# Laser_Tec_Control.net
KiCad netlist of a schematic drawn in Altium Designer
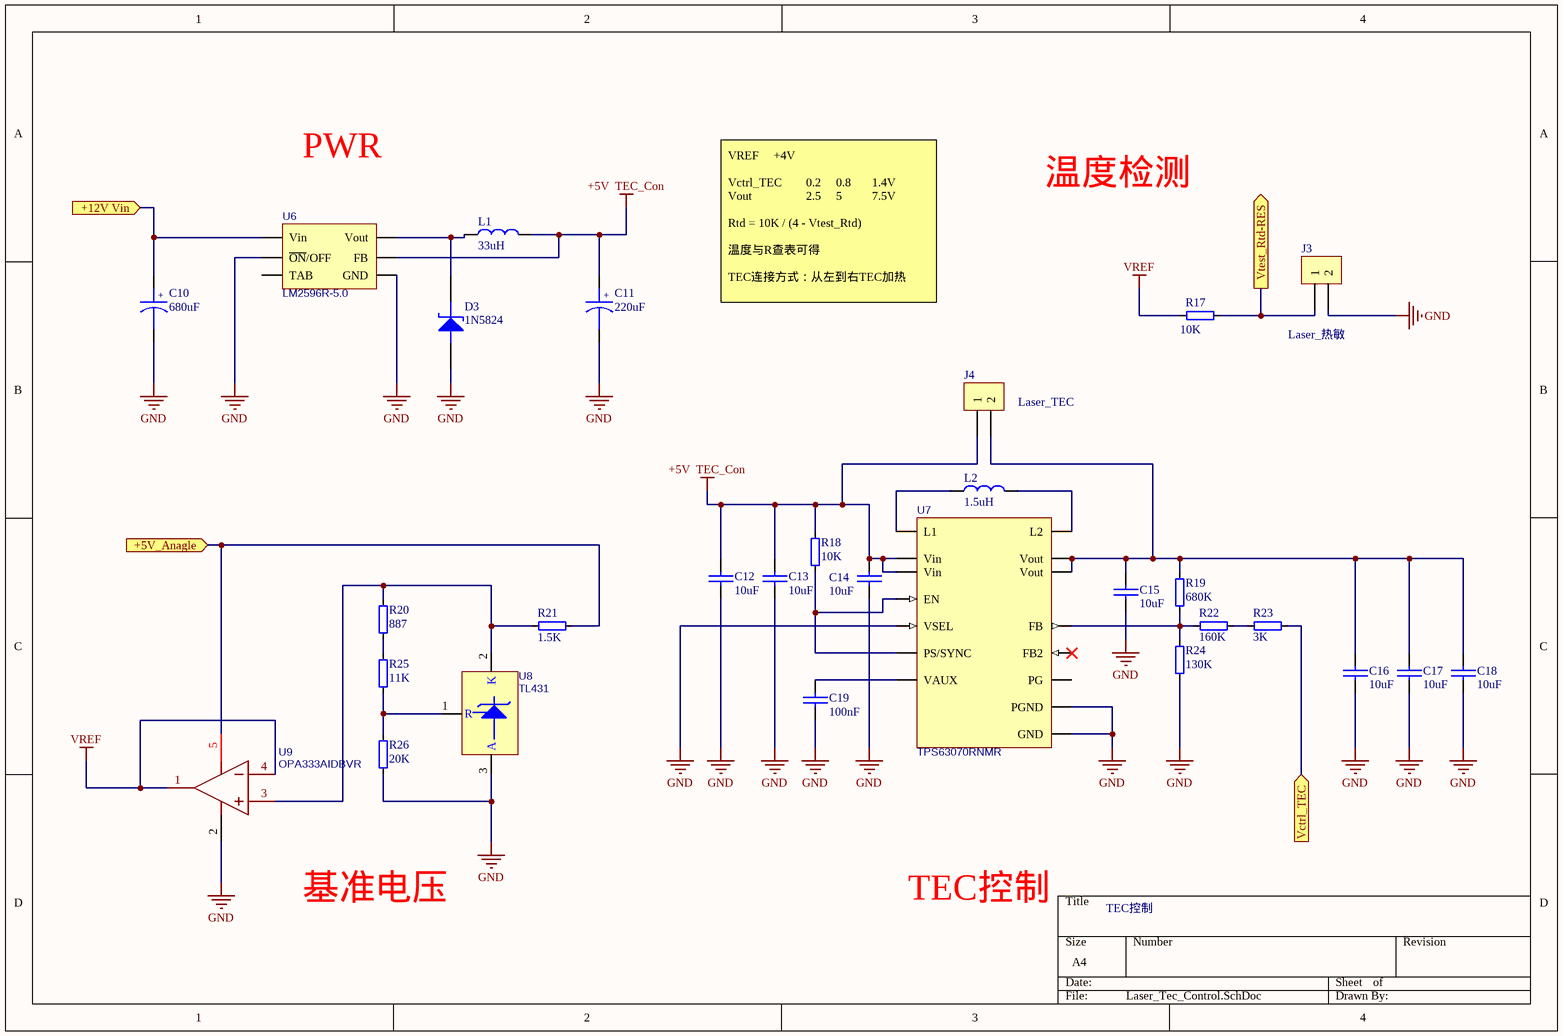
[diagram p0: Laser_Tec_Control.SchDoc]

(export (version "E")
  (design (tool "Eeschema 10.0.6"))
  (components
    (comp (ref "C10")
      (value "680uF")
      (footprint "CAP-TH_BD8.0-P3.50-D0.6-FD")
      (description "Capacitor")
      (libsource (lib "Laser Controller") (part "电解电容1"))
    )
    (comp (ref "C11")
      (value "220uF")
      (footprint "CAP-TH_BD8.0-P3.50-D0.6-FD")
      (description "Capacitor")
      (libsource (lib "Laser Controller") (part "电解电容1"))
    )
    (comp (ref "C12")
      (value "10uF")
      (footprint "C 0805_M")
      (description "Capacitor 0805")
      (libsource (lib "Laser Controller") (part "普通电容"))
    )
    (comp (ref "C13")
      (value "10uF")
      (footprint "C 0805_M")
      (description "Capacitor,0805")
      (libsource (lib "Laser Controller") (part "普通电容"))
    )
    (comp (ref "C14")
      (value "10uF")
      (footprint "C 0805_M")
      (description "Capacitor,0603")
      (libsource (lib "Laser Controller") (part "普通电容"))
    )
    (comp (ref "C15")
      (value "10uF")
      (footprint "C 0805_M")
      (description "Capacitor,0603")
      (libsource (lib "Laser Controller") (part "普通电容"))
    )
    (comp (ref "C16")
      (value "10uF")
      (footprint "C 0805_M")
      (description "Capacitor,0805")
      (libsource (lib "Laser Controller") (part "普通电容"))
    )
    (comp (ref "C17")
      (value "10uF")
      (footprint "C 0805_M")
      (description "Capacitor 0805")
      (libsource (lib "Laser Controller") (part "普通电容"))
    )
    (comp (ref "C18")
      (value "10uF")
      (footprint "C 0805_M")
      (description "Capacitor 0805")
      (libsource (lib "Laser Controller") (part "普通电容"))
    )
    (comp (ref "C19")
      (value "100nF")
      (footprint "C 0805_M")
      (description "Capacitor")
      (libsource (lib "Laser Controller") (part "普通电容"))
    )
    (comp (ref "D3")
      (value "1N5824")
      (footprint "SMA_L4.3-W2.6-LS5.0-RD")
      (description "Zener Diode")
      (libsource (lib "Laser Controller") (part "1N5824"))
    )
    (comp (ref "J3")
      (value "Laser_热敏")
      (footprint "KF128-5.08-2P")
      (description "jointbar")
      (libsource (lib "Laser Controller") (part "SIP2"))
    )
    (comp (ref "J4")
      (value "Laser_TEC")
      (footprint "KF128-5.08-2P")
      (description "jointbar")
      (libsource (lib "Laser Controller") (part "SIP2"))
    )
    (comp (ref "L1")
      (value "33uH")
      (footprint "L 0805")
      (description "电感")
      (libsource (lib "Laser Controller") (part "L1"))
    )
    (comp (ref "L2")
      (value "1.5uH")
      (footprint "L 0805")
      (description "电感")
      (libsource (lib "Laser Controller") (part "L1"))
    )
    (comp (ref "R17") (value "10K") (footprint "0805R") (libsource (lib "Laser Controller") (part "普通电阻")))
    (comp (ref "R18") (value "10K") (footprint "0805R") (libsource (lib "Laser Controller") (part "普通电阻")))
    (comp (ref "R19") (value "680K") (footprint "0805R") (libsource (lib "Laser Controller") (part "普通电阻")))
    (comp (ref "R20") (value "887") (footprint "0805R") (libsource (lib "Laser Controller") (part "普通电阻")))
    (comp (ref "R21") (value "1.5K") (footprint "0805R") (libsource (lib "Laser Controller") (part "普通电阻")))
    (comp (ref "R22") (value "160K") (footprint "0805R") (libsource (lib "Laser Controller") (part "普通电阻")))
    (comp (ref "R23") (value "3K") (footprint "0805R") (libsource (lib "Laser Controller") (part "普通电阻")))
    (comp (ref "R24") (value "130K") (footprint "0805R") (libsource (lib "Laser Controller") (part "普通电阻")))
    (comp (ref "R25") (value "11K") (footprint "0805R") (libsource (lib "Laser Controller") (part "普通电阻")))
    (comp (ref "R26") (value "20K") (footprint "0805R") (libsource (lib "Laser Controller") (part "普通电阻")))
    (comp (ref "U6")
      (value "LM2596R-5.0")
      (footprint "TO-263-5_L10.2-W8.6-P1.70-LS14.4-TL")
      (fields (field (name "BOM_SUPPLIER PART") "C77782"))
      (libsource (lib "Laser Controller") (part "LM2596R-5.0"))
    )
    (comp (ref "U7")
      (value "TPS63070RNMR")
      (footprint "VQFN-HR-15_L3.0-W2.5-P0.50-BL_TPS63070RNMR")
      (fields (field (name "BOM_SUPPLIER PART") "C109322"))
      (libsource (lib "Laser Controller") (part "TPS63070RNMR"))
    )
    (comp (ref "U8")
      (value "TL431")
      (footprint "SOT-23-3_L2.9-W1.4-P1.90-LS2.6-BR")
      (fields (field (name "BOM_SUPPLIER PART") "C963380") (field (name "CONTRIBUTOR") "LCSC"))
      (libsource (lib "Laser Controller") (part "TL431"))
    )
    (comp (ref "U9")
      (value "OPA333AIDBVR")
      (footprint "SOT-23-5_L3.0-W1.7-P0.95-LS2.8-BR")
      (fields (field (name "BOM_SUPPLIER PART") "C30878") (field (name "CONTRIBUTOR") "LCSC"))
      (libsource (lib "Laser Controller") (part "OPA333AIDBVR"))
    )
  )
  (nets
    (net (code "1") (name "+5V  TEC_Con") (class "Default")
      (node (ref "C11") (pin "1") (pinfunction "1_1") (pintype "passive"))
      (node (ref "C12") (pin "1") (pinfunction "1_1") (pintype "passive"))
      (node (ref "C13") (pin "1") (pinfunction "1_1") (pintype "passive"))
      (node (ref "C14") (pin "1") (pinfunction "1_1") (pintype "passive"))
      (node (ref "J4") (pin "1") (pinfunction "1_1") (pintype "passive"))
      (node (ref "L1") (pin "1") (pinfunction "1_1") (pintype "passive"))
      (node (ref "R18") (pin "2") (pinfunction "2_2") (pintype "passive"))
      (node (ref "U6") (pin "4") (pinfunction "FB_4") (pintype "passive"))
      (node (ref "U7") (pin "12") (pinfunction "Vin_12") (pintype "passive"))
      (node (ref "U7") (pin "13") (pinfunction "Vin_13") (pintype "passive"))
    )
    (net (code "2") (name "/+5V_Anagle") (class "Default")
      (node (ref "R21") (pin "1") (pinfunction "1_1") (pintype "passive"))
      (node (ref "U9") (pin "5") (pinfunction "V+_5") (pintype "passive"))
    )
    (net (code "3") (name "/+12V Vin") (class "Default")
      (node (ref "C10") (pin "1") (pinfunction "1_1") (pintype "passive"))
      (node (ref "U6") (pin "1") (pinfunction "Vin_1") (pintype "passive"))
    )
    (net (code "4") (name "/Vctrl_TEC") (class "Default")
      (node (ref "R23") (pin "1") (pinfunction "1_1") (pintype "passive"))
    )
    (net (code "5") (name "/Vtest_Rtd-RES") (class "Default")
      (node (ref "J3") (pin "1") (pinfunction "1_1") (pintype "passive"))
      (node (ref "R17") (pin "2") (pinfunction "2_2") (pintype "passive"))
    )
    (net (code "6") (name "GND") (class "Default")
      (node (ref "C10") (pin "2") (pinfunction "2_2") (pintype "passive"))
      (node (ref "C11") (pin "2") (pinfunction "2_2") (pintype "passive"))
      (node (ref "C12") (pin "2") (pinfunction "2_2") (pintype "passive"))
      (node (ref "C13") (pin "2") (pinfunction "2_2") (pintype "passive"))
      (node (ref "C14") (pin "2") (pinfunction "2_2") (pintype "passive"))
      (node (ref "C15") (pin "2") (pinfunction "2_2") (pintype "passive"))
      (node (ref "C16") (pin "2") (pinfunction "2_2") (pintype "passive"))
      (node (ref "C17") (pin "2") (pinfunction "2_2") (pintype "passive"))
      (node (ref "C18") (pin "2") (pinfunction "2_2") (pintype "passive"))
      (node (ref "C19") (pin "2") (pinfunction "2_2") (pintype "passive"))
      (node (ref "D3") (pin "1") (pinfunction "A_1") (pintype "passive"))
      (node (ref "J3") (pin "2") (pinfunction "2_2") (pintype "passive"))
      (node (ref "R24") (pin "1") (pinfunction "1_1") (pintype "passive"))
      (node (ref "R26") (pin "1") (pinfunction "1_1") (pintype "passive"))
      (node (ref "U6") (pin "3") (pinfunction "GND_3") (pintype "passive"))
      (node (ref "U6") (pin "5") (pinfunction "~{ON}/OFF_5") (pintype "passive"))
      (node (ref "U7") (pin "10") (pinfunction "PGND_10") (pintype "passive"))
      (node (ref "U7") (pin "15") (pinfunction "VSEL_15") (pintype "input"))
      (node (ref "U7") (pin "4") (pinfunction "GND_4") (pintype "passive"))
      (node (ref "U8") (pin "3") (pinfunction "A_3") (pintype "passive"))
      (node (ref "U9") (pin "2") (pinfunction "V-_2") (pintype "passive"))
    )
    (net (code "7") (name "Net-(C15-Pad1)") (class "Default")
      (node (ref "C15") (pin "1") (pinfunction "1_1") (pintype "passive"))
      (node (ref "C16") (pin "1") (pinfunction "1_1") (pintype "passive"))
      (node (ref "C17") (pin "1") (pinfunction "1_1") (pintype "passive"))
      (node (ref "C18") (pin "1") (pinfunction "1_1") (pintype "passive"))
      (node (ref "J4") (pin "2") (pinfunction "2_2") (pintype "passive"))
      (node (ref "R19") (pin "2") (pinfunction "2_2") (pintype "passive"))
      (node (ref "U7") (pin "7") (pinfunction "Vout_7") (pintype "passive"))
      (node (ref "U7") (pin "8") (pinfunction "Vout_8") (pintype "passive"))
    )
    (net (code "8") (name "Net-(D3-K)") (class "Default")
      (node (ref "D3") (pin "2") (pinfunction "K_2") (pintype "passive"))
      (node (ref "L1") (pin "2") (pinfunction "2_2") (pintype "passive"))
      (node (ref "U6") (pin "2") (pinfunction "Vout_2") (pintype "passive"))
    )
    (net (code "9") (name "Net-(R20-Pad1)") (class "Default")
      (node (ref "R20") (pin "1") (pinfunction "1_1") (pintype "passive"))
      (node (ref "R25") (pin "2") (pinfunction "2_2") (pintype "passive"))
    )
    (net (code "10") (name "Net-(R22-Pad1)") (class "Default")
      (node (ref "R22") (pin "1") (pinfunction "1_1") (pintype "passive"))
      (node (ref "R23") (pin "2") (pinfunction "2_2") (pintype "passive"))
    )
    (net (code "11") (name "Net-(U7-EN)") (class "Default")
      (node (ref "R18") (pin "1") (pinfunction "1_1") (pintype "passive"))
      (node (ref "U7") (pin "1") (pinfunction "PS/SYNC_1") (pintype "passive"))
      (node (ref "U7") (pin "14") (pinfunction "EN_14") (pintype "input"))
    )
    (net (code "12") (name "Net-(U7-FB)") (class "Default")
      (node (ref "R19") (pin "1") (pinfunction "1_1") (pintype "passive"))
      (node (ref "R22") (pin "2") (pinfunction "2_2") (pintype "passive"))
      (node (ref "R24") (pin "2") (pinfunction "2_2") (pintype "passive"))
      (node (ref "U7") (pin "5") (pinfunction "FB_5") (pintype "output"))
    )
    (net (code "13") (name "Net-(U7-L1)") (class "Default")
      (node (ref "L2") (pin "2") (pinfunction "2_2") (pintype "passive"))
      (node (ref "U7") (pin "11") (pinfunction "L1_11") (pintype "passive"))
    )
    (net (code "14") (name "Net-(U7-L2)") (class "Default")
      (node (ref "L2") (pin "1") (pinfunction "1_1") (pintype "passive"))
      (node (ref "U7") (pin "9") (pinfunction "L2_9") (pintype "passive"))
    )
    (net (code "15") (name "Net-(U7-VAUX)") (class "Default")
      (node (ref "C19") (pin "1") (pinfunction "1_1") (pintype "passive"))
      (node (ref "U7") (pin "3") (pinfunction "VAUX_3") (pintype "passive"))
    )
    (net (code "16") (name "Net-(U8-K)") (class "Default")
      (node (ref "R20") (pin "2") (pinfunction "2_2") (pintype "passive"))
      (node (ref "R21") (pin "2") (pinfunction "2_2") (pintype "passive"))
      (node (ref "U8") (pin "2") (pinfunction "K_2") (pintype "passive"))
      (node (ref "U9") (pin "3") (pinfunction "IN+_3") (pintype "passive"))
    )
    (net (code "17") (name "Net-(U8-R)") (class "Default")
      (node (ref "R25") (pin "1") (pinfunction "1_1") (pintype "passive"))
      (node (ref "R26") (pin "2") (pinfunction "2_2") (pintype "passive"))
      (node (ref "U8") (pin "1") (pinfunction "R_1") (pintype "passive"))
    )
    (net (code "18") (name "VREF") (class "Default")
      (node (ref "R17") (pin "1") (pinfunction "1_1") (pintype "passive"))
      (node (ref "U9") (pin "1") (pinfunction "OUT_1") (pintype "passive"))
      (node (ref "U9") (pin "4") (pinfunction "IN-_4") (pintype "passive"))
    )
    (net (code "19") (name "unconnected-(U6-TAB-Pad6)") (class "Default")
      (node (ref "U6") (pin "6") (pinfunction "TAB_6") (pintype "passive"))
    )
    (net (code "20") (name "unconnected-(U7-FB2-Pad6)") (class "Default")
      (node (ref "U7") (pin "6") (pinfunction "FB2_6") (pintype "input+no_connect"))
    )
    (net (code "21") (name "unconnected-(U7-PG-Pad2)") (class "Default")
      (node (ref "U7") (pin "2") (pinfunction "PG_2") (pintype "passive"))
    )
  )
)
